# 3_RS232.net
KiCad netlist of a schematic drawn in EAGLE
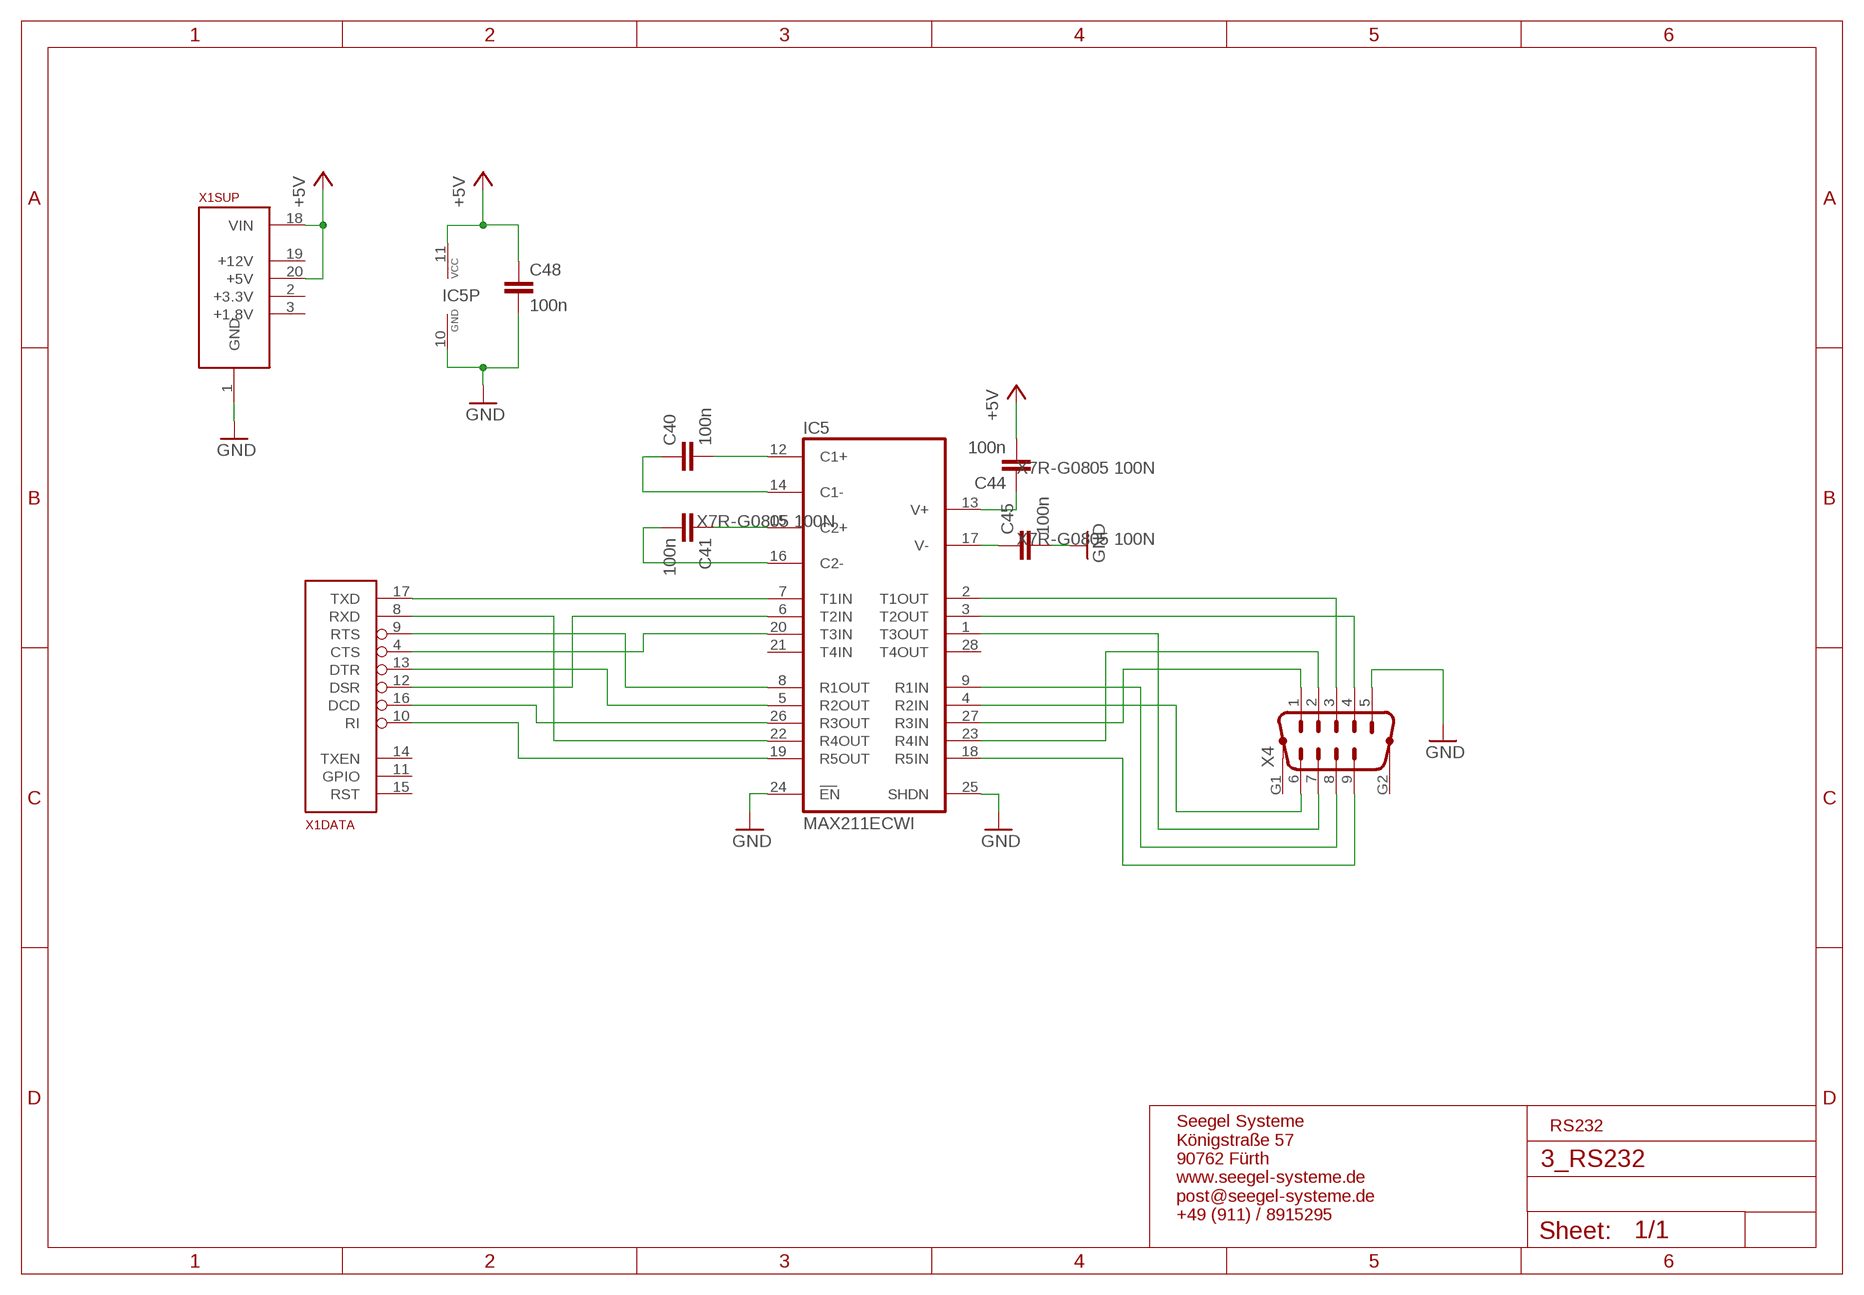
[diagram p0: schematic, sheet 1]

(export (version "E")
  (design (tool "Eeschema 10.0.6"))
  (components
    (comp (ref "C40")
      (value "100n")
      (footprint "eagle-import:C0805")
      (libsource (lib "eagle-import") (part "C-EUC0805"))
    )
    (comp (ref "C41")
      (value "100n")
      (footprint "eagle-import:C0805")
      (fields (field (name "OC_REICHELT") "X7R-G0805 100N"))
      (libsource (lib "eagle-import") (part "C-EUC0805"))
    )
    (comp (ref "C44")
      (value "100n")
      (footprint "eagle-import:C0805")
      (fields (field (name "OC_REICHELT") "X7R-G0805 100N"))
      (libsource (lib "eagle-import") (part "C-EUC0805"))
    )
    (comp (ref "C45")
      (value "100n")
      (footprint "eagle-import:C0805")
      (fields (field (name "OC_REICHELT") "X7R-G0805 100N"))
      (libsource (lib "eagle-import") (part "C-EUC0805"))
    )
    (comp (ref "C48")
      (value "100n")
      (footprint "eagle-import:C0805")
      (libsource (lib "eagle-import") (part "C-EUC0805"))
    )
    (comp (ref "IC5")
      (value "MAX211ECWI")
      (footprint "eagle-import:SO28L")
      (fields (field (name "MPN") "MAX211ECWI+T") (field (name "OC_FARNELL") "2519263"))
      (libsource (lib "eagle-import") (part "MAX211ECWI"))
    )
    (comp (ref "X1")
      (value "ALLSERIALSLAVE")
      (footprint "eagle-import:DAUGHTER-THT")
      (libsource (lib "eagle-import") (part "ALLSERIALSLAVE"))
    )
    (comp (ref "X4")
      (value "M09HP")
      (footprint "eagle-import:M09HP")
      (libsource (lib "eagle-import") (part "M09HP"))
    )
  )
  (nets
    (net (code "1") (name "+5V") (class "Default")
      (node (ref "C44") (pin "2") (pinfunction "2_2") (pintype "passive"))
      (node (ref "C48") (pin "1") (pinfunction "1_1") (pintype "passive"))
      (node (ref "IC5") (pin "11") (pinfunction "VCC_11") (pintype "power_in"))
      (node (ref "X1") (pin "18") (pinfunction "VIN_18") (pintype "bidirectional"))
      (node (ref "X1") (pin "20") (pinfunction "+5V_20") (pintype "bidirectional"))
    )
    (net (code "2") (name "GND") (class "Default")
      (node (ref "C45") (pin "2") (pinfunction "2_2") (pintype "passive"))
      (node (ref "C48") (pin "2") (pinfunction "2_2") (pintype "passive"))
      (node (ref "IC5") (pin "10") (pinfunction "GND_10") (pintype "power_in"))
      (node (ref "IC5") (pin "24") (pinfunction "EN_24") (pintype "input"))
      (node (ref "IC5") (pin "25") (pinfunction "SHDN_25") (pintype "input"))
      (node (ref "X1") (pin "1") (pinfunction "GND_1") (pintype "bidirectional"))
      (node (ref "X4") (pin "5") (pinfunction "5_5") (pintype "passive"))
    )
    (net (code "3") (name "Net-(IC5A-C1+)") (class "Default")
      (node (ref "C40") (pin "2") (pinfunction "2_2") (pintype "passive"))
      (node (ref "IC5") (pin "12") (pinfunction "C1+_12") (pintype "passive"))
    )
    (net (code "4") (name "Net-(IC5A-C1-)") (class "Default")
      (node (ref "C40") (pin "1") (pinfunction "1_1") (pintype "passive"))
      (node (ref "IC5") (pin "14") (pinfunction "C1-_14") (pintype "passive"))
    )
    (net (code "5") (name "Net-(IC5A-C2+)") (class "Default")
      (node (ref "C41") (pin "1") (pinfunction "1_1") (pintype "passive"))
      (node (ref "IC5") (pin "15") (pinfunction "C2+_15") (pintype "passive"))
    )
    (net (code "6") (name "Net-(IC5A-C2-)") (class "Default")
      (node (ref "C41") (pin "2") (pinfunction "2_2") (pintype "passive"))
      (node (ref "IC5") (pin "16") (pinfunction "C2-_16") (pintype "passive"))
    )
    (net (code "7") (name "Net-(IC5A-R1IN)") (class "Default")
      (node (ref "IC5") (pin "9") (pinfunction "R1IN_9") (pintype "input"))
      (node (ref "X4") (pin "8") (pinfunction "8_8") (pintype "passive"))
    )
    (net (code "8") (name "Net-(IC5A-R1OUT)") (class "Default")
      (node (ref "IC5") (pin "8") (pinfunction "R1OUT_8") (pintype "output"))
      (node (ref "X1") (pin "9") (pinfunction "RTS_9") (pintype "output"))
    )
    (net (code "9") (name "Net-(IC5A-R2IN)") (class "Default")
      (node (ref "IC5") (pin "4") (pinfunction "R2IN_4") (pintype "input"))
      (node (ref "X4") (pin "6") (pinfunction "6_6") (pintype "passive"))
    )
    (net (code "10") (name "Net-(IC5A-R2OUT)") (class "Default")
      (node (ref "IC5") (pin "5") (pinfunction "R2OUT_5") (pintype "output"))
      (node (ref "X1") (pin "13") (pinfunction "DTR_13") (pintype "output"))
    )
    (net (code "11") (name "Net-(IC5A-R3IN)") (class "Default")
      (node (ref "IC5") (pin "27") (pinfunction "R3IN_27") (pintype "input"))
      (node (ref "X4") (pin "1") (pinfunction "1_1") (pintype "passive"))
    )
    (net (code "12") (name "Net-(IC5A-R3OUT)") (class "Default")
      (node (ref "IC5") (pin "26") (pinfunction "R3OUT_26") (pintype "output"))
      (node (ref "X1") (pin "16") (pinfunction "DCD_16") (pintype "input"))
    )
    (net (code "13") (name "Net-(IC5A-R4IN)") (class "Default")
      (node (ref "IC5") (pin "23") (pinfunction "R4IN_23") (pintype "input"))
      (node (ref "X4") (pin "2") (pinfunction "2_2") (pintype "passive"))
    )
    (net (code "14") (name "Net-(IC5A-R4OUT)") (class "Default")
      (node (ref "IC5") (pin "22") (pinfunction "R4OUT_22") (pintype "output"))
      (node (ref "X1") (pin "8") (pinfunction "RXD_8") (pintype "input"))
    )
    (net (code "15") (name "Net-(IC5A-R5IN)") (class "Default")
      (node (ref "IC5") (pin "18") (pinfunction "R5IN_18") (pintype "input"))
      (node (ref "X4") (pin "9") (pinfunction "9_9") (pintype "passive"))
    )
    (net (code "16") (name "Net-(IC5A-R5OUT)") (class "Default")
      (node (ref "IC5") (pin "19") (pinfunction "R5OUT_19") (pintype "output"))
      (node (ref "X1") (pin "10") (pinfunction "RI_10") (pintype "input"))
    )
    (net (code "17") (name "Net-(IC5A-T1IN)") (class "Default")
      (node (ref "IC5") (pin "7") (pinfunction "T1IN_7") (pintype "input"))
      (node (ref "X1") (pin "17") (pinfunction "TXD_17") (pintype "output"))
    )
    (net (code "18") (name "Net-(IC5A-T1OUT)") (class "Default")
      (node (ref "IC5") (pin "2") (pinfunction "T1OUT_2") (pintype "output"))
      (node (ref "X4") (pin "3") (pinfunction "3_3") (pintype "passive"))
    )
    (net (code "19") (name "Net-(IC5A-T2IN)") (class "Default")
      (node (ref "IC5") (pin "6") (pinfunction "T2IN_6") (pintype "input"))
      (node (ref "X1") (pin "12") (pinfunction "DSR_12") (pintype "input"))
    )
    (net (code "20") (name "Net-(IC5A-T2OUT)") (class "Default")
      (node (ref "IC5") (pin "3") (pinfunction "T2OUT_3") (pintype "output"))
      (node (ref "X4") (pin "4") (pinfunction "4_4") (pintype "passive"))
    )
    (net (code "21") (name "Net-(IC5A-T3IN)") (class "Default")
      (node (ref "IC5") (pin "20") (pinfunction "T3IN_20") (pintype "input"))
      (node (ref "X1") (pin "4") (pinfunction "CTS_4") (pintype "input"))
    )
    (net (code "22") (name "Net-(IC5A-T3OUT)") (class "Default")
      (node (ref "IC5") (pin "1") (pinfunction "T3OUT_1") (pintype "output"))
      (node (ref "X4") (pin "7") (pinfunction "7_7") (pintype "passive"))
    )
    (net (code "23") (name "Net-(IC5A-V+)") (class "Default")
      (node (ref "C44") (pin "1") (pinfunction "1_1") (pintype "passive"))
      (node (ref "IC5") (pin "13") (pinfunction "V+_13") (pintype "passive"))
    )
    (net (code "24") (name "Net-(IC5A-V-)") (class "Default")
      (node (ref "C45") (pin "1") (pinfunction "1_1") (pintype "passive"))
      (node (ref "IC5") (pin "17") (pinfunction "V-_17") (pintype "passive"))
    )
    (net (code "25") (name "unconnected-(IC5A-T4IN-Pad21)") (class "Default")
      (node (ref "IC5") (pin "21") (pinfunction "T4IN_21") (pintype "input"))
    )
    (net (code "26") (name "unconnected-(IC5A-T4OUT-Pad28)") (class "Default")
      (node (ref "IC5") (pin "28") (pinfunction "T4OUT_28") (pintype "output"))
    )
    (net (code "27") (name "unconnected-(X1A-GPIO-Pad11)") (class "Default")
      (node (ref "X1") (pin "11") (pinfunction "GPIO_11") (pintype "bidirectional"))
    )
    (net (code "28") (name "unconnected-(X1A-RST-Pad15)") (class "Default")
      (node (ref "X1") (pin "15") (pinfunction "RST_15") (pintype "bidirectional"))
    )
    (net (code "29") (name "unconnected-(X1A-TXEN-Pad14)") (class "Default")
      (node (ref "X1") (pin "14") (pinfunction "TXEN_14") (pintype "output"))
    )
    (net (code "30") (name "unconnected-(X1B-+1.8V-Pad3)") (class "Default")
      (node (ref "X1") (pin "3") (pinfunction "+1.8V_3") (pintype "bidirectional"))
    )
    (net (code "31") (name "unconnected-(X1B-+3.3V-Pad2)") (class "Default")
      (node (ref "X1") (pin "2") (pinfunction "+3.3V_2") (pintype "bidirectional"))
    )
    (net (code "32") (name "unconnected-(X1B-+12V-Pad19)") (class "Default")
      (node (ref "X1") (pin "19") (pinfunction "+12V_19") (pintype "bidirectional"))
    )
    (net (code "33") (name "unconnected-(X4-PadG1)") (class "Default")
      (node (ref "X4") (pin "G1") (pinfunction "G1_G1") (pintype "passive"))
    )
    (net (code "34") (name "unconnected-(X4-PadG2)") (class "Default")
      (node (ref "X4") (pin "G2") (pinfunction "G2_G2") (pintype "passive"))
    )
  )
)
